# doublesidedflasher.net
KiCad netlist of a schematic drawn in EAGLE
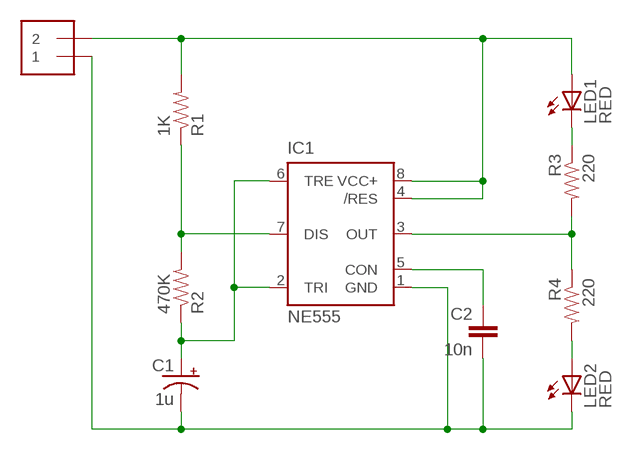
[diagram p0: schematic, sheet 1]

(export (version "E")
  (design (tool "Eeschema 10.0.6"))
  (components
    (comp (ref "C1")
      (value "1u")
      (footprint "eagle-import:CPOL-RADIAL-10UF-25V")
      (libsource (lib "eagle-import") (part "CAP_POLPTH2"))
    )
    (comp (ref "C2")
      (value "10n")
      (footprint "eagle-import:CAP-PTH-SMALL")
      (libsource (lib "eagle-import") (part "CAPPTH"))
    )
    (comp (ref "IC1")
      (value "NE555")
      (footprint "eagle-import:DIL-08")
      (fields (field (name "MF") "Arrow Electronics") (field (name "MPN") "NE555N"))
      (libsource (lib "eagle-import") (part "NE555"))
    )
    (comp (ref "J1")
      (value "1X2-3.5MM")
      (footprint "eagle-import:1X2-3.5MM")
      (libsource (lib "eagle-import") (part "1X2-3.5MM"))
    )
    (comp (ref "LED1")
      (value "RED")
      (footprint "eagle-import:LED5MM")
      (libsource (lib "eagle-import") (part "LED5MM"))
    )
    (comp (ref "LED2")
      (value "RED")
      (footprint "eagle-import:LED5MM")
      (libsource (lib "eagle-import") (part "LED5MM"))
    )
    (comp (ref "R1")
      (value "1K")
      (footprint "eagle-import:AXIAL-0.3")
      (libsource (lib "eagle-import") (part "RESISTORAXIAL-0.3"))
    )
    (comp (ref "R2")
      (value "470K")
      (footprint "eagle-import:AXIAL-0.3")
      (libsource (lib "eagle-import") (part "RESISTORAXIAL-0.3"))
    )
    (comp (ref "R3")
      (value "220")
      (footprint "eagle-import:AXIAL-0.3")
      (libsource (lib "eagle-import") (part "RESISTORAXIAL-0.3"))
    )
    (comp (ref "R4")
      (value "220")
      (footprint "eagle-import:AXIAL-0.3")
      (libsource (lib "eagle-import") (part "RESISTORAXIAL-0.3"))
    )
  )
  (nets
    (net (code "1") (name "Net-(C1-+)") (class "Default")
      (node (ref "C1") (pin "1") (pinfunction "+_1") (pintype "passive"))
      (node (ref "IC1") (pin "2") (pinfunction "TRI_2") (pintype "input"))
      (node (ref "IC1") (pin "6") (pinfunction "TRE_6") (pintype "input"))
      (node (ref "R2") (pin "P$1") (pinfunction "1_P$1") (pintype "passive"))
    )
    (net (code "2") (name "Net-(C1--)") (class "Default")
      (node (ref "C1") (pin "2") (pinfunction "-_2") (pintype "passive"))
      (node (ref "C2") (pin "2") (pinfunction "2_2") (pintype "passive"))
      (node (ref "IC1") (pin "1") (pinfunction "GND_1") (pintype "power_in"))
      (node (ref "J1") (pin "1") (pinfunction "1_1") (pintype "passive"))
      (node (ref "LED2") (pin "K") (pinfunction "C_K") (pintype "passive"))
    )
    (net (code "3") (name "Net-(IC1-CON)") (class "Default")
      (node (ref "C2") (pin "1") (pinfunction "1_1") (pintype "passive"))
      (node (ref "IC1") (pin "5") (pinfunction "CON_5") (pintype "input"))
    )
    (net (code "4") (name "Net-(IC1-DIS)") (class "Default")
      (node (ref "IC1") (pin "7") (pinfunction "DIS_7") (pintype "input"))
      (node (ref "R1") (pin "P$1") (pinfunction "1_P$1") (pintype "passive"))
      (node (ref "R2") (pin "P$2") (pinfunction "2_P$2") (pintype "passive"))
    )
    (net (code "5") (name "Net-(IC1-OUT)") (class "Default")
      (node (ref "IC1") (pin "3") (pinfunction "OUT_3") (pintype "output"))
      (node (ref "R3") (pin "P$2") (pinfunction "2_P$2") (pintype "passive"))
      (node (ref "R4") (pin "P$1") (pinfunction "1_P$1") (pintype "passive"))
    )
    (net (code "6") (name "Net-(IC1-VCC+)") (class "Default")
      (node (ref "IC1") (pin "4") (pinfunction "/RES_4") (pintype "input"))
      (node (ref "IC1") (pin "8") (pinfunction "VCC+_8") (pintype "power_in"))
      (node (ref "J1") (pin "2") (pinfunction "2_2") (pintype "passive"))
      (node (ref "LED1") (pin "A") (pinfunction "A_A") (pintype "passive"))
      (node (ref "R1") (pin "P$2") (pinfunction "2_P$2") (pintype "passive"))
    )
    (net (code "7") (name "Net-(LED1-C)") (class "Default")
      (node (ref "LED1") (pin "K") (pinfunction "C_K") (pintype "passive"))
      (node (ref "R3") (pin "P$1") (pinfunction "1_P$1") (pintype "passive"))
    )
    (net (code "8") (name "Net-(R4-2)") (class "Default")
      (node (ref "LED2") (pin "A") (pinfunction "A_A") (pintype "passive"))
      (node (ref "R4") (pin "P$2") (pinfunction "2_P$2") (pintype "passive"))
    )
  )
)
